# 0-10V_Converter.net
KiCad netlist of a schematic drawn in Altium Designer
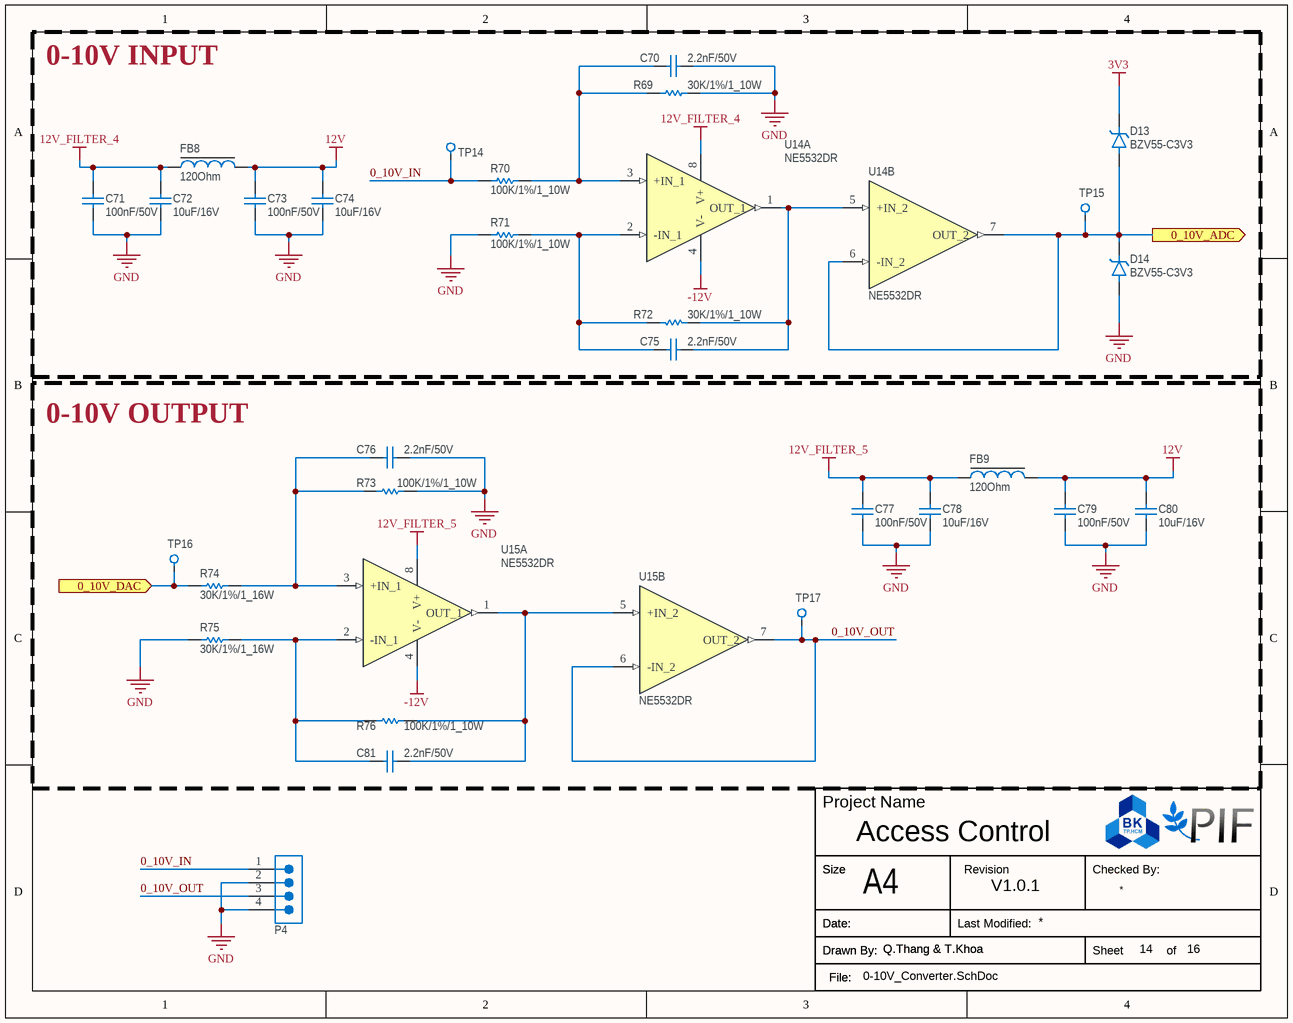
[diagram p0: 0-10V_Converter.SchDoc]

(export (version "E")
  (design (tool "Eeschema 10.0.6"))
  (components
    (comp (ref "C70")
      (value "2.2nF/50V")
      (footprint "CAP_0603")
      (description "CAP, size 0603, 2.2nF, 50V")
      (fields (field (name "SUPPLY PART NUMBER") "CC0603KRX7R9BB222"))
      (libsource (lib "BluetoothTracking") (part "Ceramic_Cap_2.2nF_50V_0603"))
    )
    (comp (ref "C71")
      (value "100nF/50V")
      (footprint "CAP_0603")
      (description "CAP, size 0603, 100nF, 50V")
      (fields (field (name "SUPPLY PART NUMBER") "Tụ Gốm 0603 100nF (0.1uF) 50V"))
      (libsource (lib "BluetoothTracking") (part "Ceramic_Cap_100nF_50V_0603"))
    )
    (comp (ref "C72")
      (value "10uF/16V")
      (footprint "CAP_0603")
      (description "CAP, size 0603, 10uF, 16V")
      (fields (field (name "SUPPLY PART NUMBER") "Tụ Gốm 0603 10uF 16V"))
      (libsource (lib "BluetoothTracking") (part "Ceramic_Cap_10uF_16V_0603"))
    )
    (comp (ref "C73")
      (value "100nF/50V")
      (footprint "CAP_0603")
      (description "CAP, size 0603, 100nF, 50V")
      (fields (field (name "SUPPLY PART NUMBER") "Tụ Gốm 0603 100nF (0.1uF) 50V"))
      (libsource (lib "BluetoothTracking") (part "Ceramic_Cap_100nF_50V_0603"))
    )
    (comp (ref "C74")
      (value "10uF/16V")
      (footprint "CAP_0603")
      (description "CAP, size 0603, 10uF, 16V")
      (fields (field (name "SUPPLY PART NUMBER") "Tụ Gốm 0603 10uF 16V"))
      (libsource (lib "BluetoothTracking") (part "Ceramic_Cap_10uF_16V_0603"))
    )
    (comp (ref "C75")
      (value "2.2nF/50V")
      (footprint "CAP_0603")
      (description "CAP, size 0603, 2.2nF, 50V")
      (fields (field (name "SUPPLY PART NUMBER") "CC0603KRX7R9BB222"))
      (libsource (lib "BluetoothTracking") (part "Ceramic_Cap_2.2nF_50V_0603"))
    )
    (comp (ref "C76")
      (value "2.2nF/50V")
      (footprint "CAP_0603")
      (description "CAP, size 0603, 2.2nF, 50V")
      (fields (field (name "SUPPLY PART NUMBER") "CC0603KRX7R9BB222"))
      (libsource (lib "BluetoothTracking") (part "Ceramic_Cap_2.2nF_50V_0603"))
    )
    (comp (ref "C77")
      (value "100nF/50V")
      (footprint "CAP_0603")
      (description "CAP, size 0603, 100nF, 50V")
      (fields (field (name "SUPPLY PART NUMBER") "Tụ Gốm 0603 100nF (0.1uF) 50V"))
      (libsource (lib "BluetoothTracking") (part "Ceramic_Cap_100nF_50V_0603"))
    )
    (comp (ref "C78")
      (value "10uF/16V")
      (footprint "CAP_0603")
      (description "CAP, size 0603, 10uF, 16V")
      (fields (field (name "SUPPLY PART NUMBER") "Tụ Gốm 0603 10uF 16V"))
      (libsource (lib "BluetoothTracking") (part "Ceramic_Cap_10uF_16V_0603"))
    )
    (comp (ref "C79")
      (value "100nF/50V")
      (footprint "CAP_0603")
      (description "CAP, size 0603, 100nF, 50V")
      (fields (field (name "SUPPLY PART NUMBER") "Tụ Gốm 0603 100nF (0.1uF) 50V"))
      (libsource (lib "BluetoothTracking") (part "Ceramic_Cap_100nF_50V_0603"))
    )
    (comp (ref "C80")
      (value "10uF/16V")
      (footprint "CAP_0603")
      (description "CAP, size 0603, 10uF, 16V")
      (fields (field (name "SUPPLY PART NUMBER") "Tụ Gốm 0603 10uF 16V"))
      (libsource (lib "BluetoothTracking") (part "Ceramic_Cap_10uF_16V_0603"))
    )
    (comp (ref "C81")
      (value "2.2nF/50V")
      (footprint "CAP_0603")
      (description "CAP, size 0603, 2.2nF, 50V")
      (fields (field (name "SUPPLY PART NUMBER") "CC0603KRX7R9BB222"))
      (libsource (lib "BluetoothTracking") (part "Ceramic_Cap_2.2nF_50V_0603"))
    )
    (comp (ref "D13")
      (value "BZV55-C3V3")
      (footprint "SOD-80")
      (description "DIODE ZENER 3.3V 500 mW")
      (libsource (lib "BluetoothTracking") (part "Diode_BZV55C3V3"))
    )
    (comp (ref "D14")
      (value "BZV55-C3V3")
      (footprint "SOD-80")
      (description "DIODE ZENER 3.3V 500 mW")
      (libsource (lib "BluetoothTracking") (part "Diode_BZV55C3V3"))
    )
    (comp (ref "FB8")
      (value "120Ohm")
      (footprint "Ferrite_Bead_0805")
      (description "Ferrite Bead, size 0805, 120Ohm, 2A")
      (fields (field (name "SUPPLY PART NUMBER") "CBW201209U121T Ferrite Beads 2A 120 Ohm 0805"))
      (libsource (lib "BluetoothTracking") (part "Ferrite_Bead_120Ohm_2A_0805"))
    )
    (comp (ref "FB9")
      (value "120Ohm")
      (footprint "Ferrite_Bead_0805")
      (description "Ferrite Bead, size 0805, 120Ohm, 2A")
      (fields (field (name "SUPPLY PART NUMBER") "CBW201209U121T Ferrite Beads 2A 120 Ohm 0805"))
      (libsource (lib "BluetoothTracking") (part "Ferrite_Bead_120Ohm_2A_0805"))
    )
    (comp (ref "P4")
      (value "3.81mm_4P")
      (footprint "Terminal_Block_3.81mm_4P")
      (description "Terminal Block THT, pitch 3.81mm, 4p, 300V 10A")
      (fields
        (field (name "SUPPLY PART NUMBER") "UL-3.81-4-R Terminal Block Plug-in Hàn PCB 4 Chân Cong 3.81mm 300V 10A ULO")
      )
      (libsource (lib "BluetoothTracking") (part "Terminal_Block_3.81mm_4P"))
    )
    (comp (ref "R69")
      (value "30K/1%/1_10W")
      (footprint "Resistor_0603")
      (description "Resistor 0603 30KOhm 1% 1_10W")
      (fields (field (name "SUPPLY PART NUMBER") "Điện Trở 30 KOhm 0603 1%"))
      (libsource (lib "BluetoothTracking") (part "Res_30K_0603_1%"))
    )
    (comp (ref "R70")
      (value "100K/1%/1_10W")
      (footprint "Resistor_0603")
      (description "Resistor 0603 100KOhm 1% 1_10W")
      (fields (field (name "SUPPLY PART NUMBER") "Điện Trở 100 KOhm 0603 1%"))
      (libsource (lib "BluetoothTracking") (part "Res_100K_0603_1%"))
    )
    (comp (ref "R71")
      (value "100K/1%/1_10W")
      (footprint "Resistor_0603")
      (description "Resistor 0603 100KOhm 1% 1_10W")
      (fields (field (name "SUPPLY PART NUMBER") "Điện Trở 100 KOhm 0603 1%"))
      (libsource (lib "BluetoothTracking") (part "Res_100K_0603_1%"))
    )
    (comp (ref "R72")
      (value "30K/1%/1_10W")
      (footprint "Resistor_0603")
      (description "Resistor 0603 30KOhm 1% 1_10W")
      (fields (field (name "SUPPLY PART NUMBER") "Điện Trở 30 KOhm 0603 1%"))
      (libsource (lib "BluetoothTracking") (part "Res_30K_0603_1%"))
    )
    (comp (ref "R73")
      (value "100K/1%/1_10W")
      (footprint "Resistor_0603")
      (description "Resistor 0603 100KOhm 1% 1_10W")
      (fields (field (name "SUPPLY PART NUMBER") "Điện Trở 100 KOhm 0603 1%"))
      (libsource (lib "BluetoothTracking") (part "Res_100K_0603_1%"))
    )
    (comp (ref "R74")
      (value "30K/1%/1_16W")
      (footprint "RESISTOR_0402")
      (description "Resistor 0402 30KOhm 1% 1_16W")
      (fields (field (name "SUPPLY PART NUMBER") "Điện Trở 30 KOhm 0402 1%"))
      (libsource (lib "BluetoothTracking") (part "Res_30K_0402_1%"))
    )
    (comp (ref "R75")
      (value "30K/1%/1_16W")
      (footprint "RESISTOR_0402")
      (description "Resistor 0402 30KOhm 1% 1_16W")
      (fields (field (name "SUPPLY PART NUMBER") "Điện Trở 30 KOhm 0402 1%"))
      (libsource (lib "BluetoothTracking") (part "Res_30K_0402_1%"))
    )
    (comp (ref "R76")
      (value "100K/1%/1_10W")
      (footprint "Resistor_0603")
      (description "Resistor 0603 100KOhm 1% 1_10W")
      (fields (field (name "SUPPLY PART NUMBER") "Điện Trở 100 KOhm 0603 1%"))
      (libsource (lib "BluetoothTracking") (part "Res_100K_0603_1%"))
    )
    (comp (ref "TP14")
      (value "0-10V_IN")
      (footprint "TestPoint_THTPad_D1.5mm_Drill0.7mm")
      (description "Test Point TEST-1BK")
      (libsource (lib "BluetoothTracking") (part "Testpoint_TH"))
    )
    (comp (ref "TP15")
      (value "0-10V_ADC")
      (footprint "TestPoint_THTPad_D1.5mm_Drill0.7mm")
      (description "Test Point TEST-1BK")
      (libsource (lib "BluetoothTracking") (part "Testpoint_TH"))
    )
    (comp (ref "TP16")
      (value "0-10V_DAC")
      (footprint "TestPoint_THTPad_D1.5mm_Drill0.7mm")
      (description "Test Point TEST-1BK")
      (libsource (lib "BluetoothTracking") (part "Testpoint_TH"))
    )
    (comp (ref "TP17")
      (value "0-10V_Output")
      (footprint "TestPoint_THTPad_D1.5mm_Drill0.7mm")
      (description "Test Point TEST-1BK")
      (libsource (lib "BluetoothTracking") (part "Testpoint_TH"))
    )
    (comp (ref "U14")
      (value "NE5532DR")
      (footprint "SOIC-8")
      (description "Low Noise Single/Dual Operational Amplifier - SOIC-8")
      (libsource (lib "BluetoothTracking") (part "NE5532DR"))
    )
    (comp (ref "U15")
      (value "NE5532DR")
      (footprint "SOIC-8")
      (description "Low Noise Single/Dual Operational Amplifier - SOIC-8")
      (libsource (lib "BluetoothTracking") (part "NE5532DR"))
    )
  )
  (nets
    (net (code "1") (name "-12V") (class "Default")
      (node (ref "U14") (pin "4") (pinfunction "V-_4") (pintype "power_in"))
      (node (ref "U15") (pin "4") (pinfunction "V-_4") (pintype "power_in"))
    )
    (net (code "2") (name "/0_10V_ADC") (class "Default")
      (node (ref "D13") (pin "A") (pinfunction "A_A") (pintype "passive"))
      (node (ref "D14") (pin "C") (pinfunction "C_C") (pintype "passive"))
      (node (ref "TP15") (pin "1") (pinfunction "1_1") (pintype "passive"))
      (node (ref "U14") (pin "6") (pinfunction "-IN_2_6") (pintype "input"))
      (node (ref "U14") (pin "7") (pinfunction "OUT_2_7") (pintype "output"))
    )
    (net (code "3") (name "/0_10V_DAC") (class "Default")
      (node (ref "R74") (pin "1") (pinfunction "1_1") (pintype "passive"))
      (node (ref "TP16") (pin "1") (pinfunction "1_1") (pintype "passive"))
    )
    (net (code "4") (name "/0_10V_IN") (class "Default")
      (node (ref "P4") (pin "1") (pinfunction "1_1") (pintype "passive"))
      (node (ref "R70") (pin "1") (pinfunction "1_1") (pintype "passive"))
      (node (ref "TP14") (pin "1") (pinfunction "1_1") (pintype "passive"))
    )
    (net (code "5") (name "/0_10V_OUT") (class "Default")
      (node (ref "P4") (pin "3") (pinfunction "3_3") (pintype "passive"))
      (node (ref "TP17") (pin "1") (pinfunction "1_1") (pintype "passive"))
      (node (ref "U15") (pin "6") (pinfunction "-IN_2_6") (pintype "input"))
      (node (ref "U15") (pin "7") (pinfunction "OUT_2_7") (pintype "output"))
    )
    (net (code "6") (name "3V3") (class "Default")
      (node (ref "D13") (pin "C") (pinfunction "C_C") (pintype "passive"))
    )
    (net (code "7") (name "12V") (class "Default")
      (node (ref "C73") (pin "2") (pinfunction "2_2") (pintype "passive"))
      (node (ref "C74") (pin "2") (pinfunction "2_2") (pintype "passive"))
      (node (ref "C79") (pin "2") (pinfunction "2_2") (pintype "passive"))
      (node (ref "C80") (pin "2") (pinfunction "2_2") (pintype "passive"))
      (node (ref "FB8") (pin "2") (pinfunction "2_2") (pintype "passive"))
      (node (ref "FB9") (pin "2") (pinfunction "2_2") (pintype "passive"))
    )
    (net (code "8") (name "12V_FILTER_4") (class "Default")
      (node (ref "C71") (pin "2") (pinfunction "2_2") (pintype "passive"))
      (node (ref "C72") (pin "2") (pinfunction "2_2") (pintype "passive"))
      (node (ref "FB8") (pin "1") (pinfunction "1_1") (pintype "passive"))
      (node (ref "U14") (pin "8") (pinfunction "V+_8") (pintype "power_in"))
    )
    (net (code "9") (name "12V_FILTER_5") (class "Default")
      (node (ref "C77") (pin "2") (pinfunction "2_2") (pintype "passive"))
      (node (ref "C78") (pin "2") (pinfunction "2_2") (pintype "passive"))
      (node (ref "FB9") (pin "1") (pinfunction "1_1") (pintype "passive"))
      (node (ref "U15") (pin "8") (pinfunction "V+_8") (pintype "power_in"))
    )
    (net (code "10") (name "GND") (class "Default")
      (node (ref "C70") (pin "2") (pinfunction "2_2") (pintype "passive"))
      (node (ref "C71") (pin "1") (pinfunction "1_1") (pintype "passive"))
      (node (ref "C72") (pin "1") (pinfunction "1_1") (pintype "passive"))
      (node (ref "C73") (pin "1") (pinfunction "1_1") (pintype "passive"))
      (node (ref "C74") (pin "1") (pinfunction "1_1") (pintype "passive"))
      (node (ref "C76") (pin "2") (pinfunction "2_2") (pintype "passive"))
      (node (ref "C77") (pin "1") (pinfunction "1_1") (pintype "passive"))
      (node (ref "C78") (pin "1") (pinfunction "1_1") (pintype "passive"))
      (node (ref "C79") (pin "1") (pinfunction "1_1") (pintype "passive"))
      (node (ref "C80") (pin "1") (pinfunction "1_1") (pintype "passive"))
      (node (ref "D14") (pin "A") (pinfunction "A_A") (pintype "passive"))
      (node (ref "P4") (pin "2") (pinfunction "2_2") (pintype "passive"))
      (node (ref "P4") (pin "4") (pinfunction "4_4") (pintype "passive"))
      (node (ref "R69") (pin "2") (pinfunction "2_2") (pintype "passive"))
      (node (ref "R71") (pin "1") (pinfunction "1_1") (pintype "passive"))
      (node (ref "R73") (pin "2") (pinfunction "2_2") (pintype "passive"))
      (node (ref "R75") (pin "1") (pinfunction "1_1") (pintype "passive"))
    )
    (net (code "11") (name "Net-(U14A-+IN_1)") (class "Default")
      (node (ref "C70") (pin "1") (pinfunction "1_1") (pintype "passive"))
      (node (ref "R69") (pin "1") (pinfunction "1_1") (pintype "passive"))
      (node (ref "R70") (pin "2") (pinfunction "2_2") (pintype "passive"))
      (node (ref "U14") (pin "3") (pinfunction "+IN_1_3") (pintype "input"))
    )
    (net (code "12") (name "Net-(U14A--IN_1)") (class "Default")
      (node (ref "C75") (pin "1") (pinfunction "1_1") (pintype "passive"))
      (node (ref "R71") (pin "2") (pinfunction "2_2") (pintype "passive"))
      (node (ref "R72") (pin "1") (pinfunction "1_1") (pintype "passive"))
      (node (ref "U14") (pin "2") (pinfunction "-IN_1_2") (pintype "input"))
    )
    (net (code "13") (name "Net-(U14A-OUT_1)") (class "Default")
      (node (ref "C75") (pin "2") (pinfunction "2_2") (pintype "passive"))
      (node (ref "R72") (pin "2") (pinfunction "2_2") (pintype "passive"))
      (node (ref "U14") (pin "1") (pinfunction "OUT_1_1") (pintype "output"))
      (node (ref "U14") (pin "5") (pinfunction "+IN_2_5") (pintype "input"))
    )
    (net (code "14") (name "Net-(U15A-+IN_1)") (class "Default")
      (node (ref "C76") (pin "1") (pinfunction "1_1") (pintype "passive"))
      (node (ref "R73") (pin "1") (pinfunction "1_1") (pintype "passive"))
      (node (ref "R74") (pin "2") (pinfunction "2_2") (pintype "passive"))
      (node (ref "U15") (pin "3") (pinfunction "+IN_1_3") (pintype "input"))
    )
    (net (code "15") (name "Net-(U15A--IN_1)") (class "Default")
      (node (ref "C81") (pin "1") (pinfunction "1_1") (pintype "passive"))
      (node (ref "R75") (pin "2") (pinfunction "2_2") (pintype "passive"))
      (node (ref "R76") (pin "1") (pinfunction "1_1") (pintype "passive"))
      (node (ref "U15") (pin "2") (pinfunction "-IN_1_2") (pintype "input"))
    )
    (net (code "16") (name "Net-(U15A-OUT_1)") (class "Default")
      (node (ref "C81") (pin "2") (pinfunction "2_2") (pintype "passive"))
      (node (ref "R76") (pin "2") (pinfunction "2_2") (pintype "passive"))
      (node (ref "U15") (pin "1") (pinfunction "OUT_1_1") (pintype "output"))
      (node (ref "U15") (pin "5") (pinfunction "+IN_2_5") (pintype "input"))
    )
  )
)
